# Shift_register.net
KiCad netlist of a schematic drawn in Altium Designer
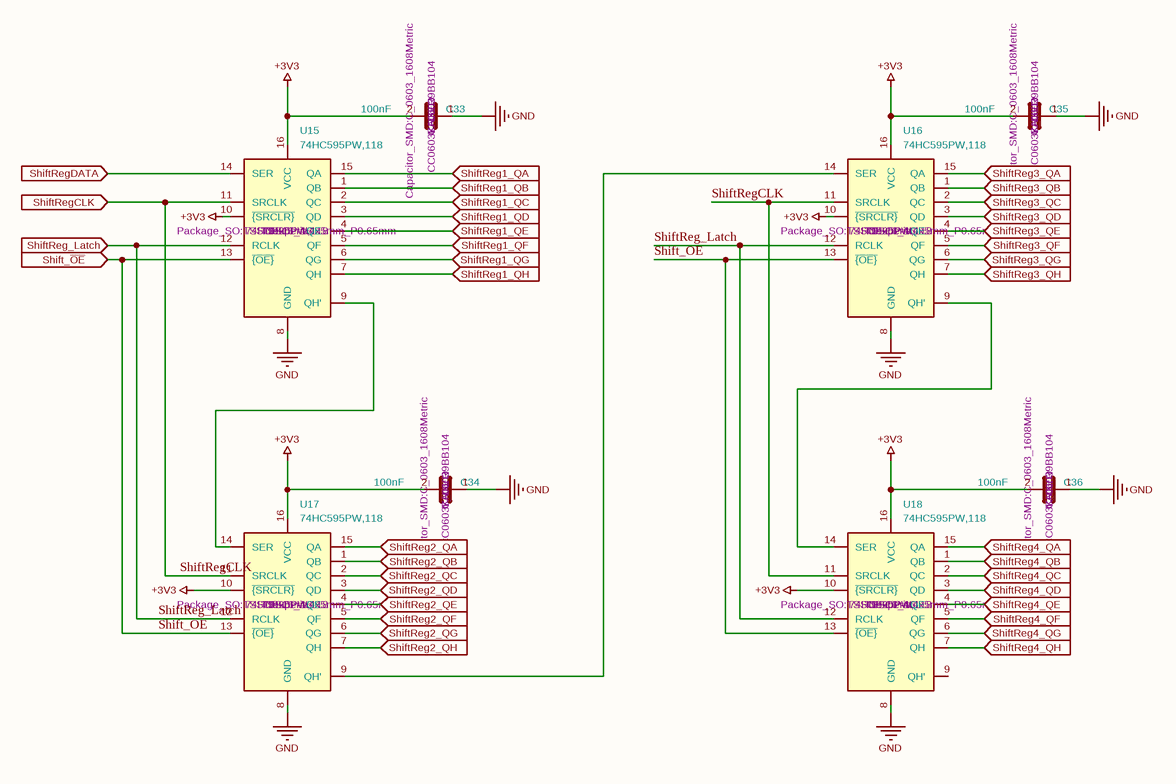
[diagram p0: Shift register.SchDoc]

(export (version "E")
  (design (tool "Eeschema 10.0.6"))
  (components
    (comp (ref "C33")
      (value "100nF")
      (footprint "Capacitor_SMD:C_0603_1608Metric")
      (fields
        (field (name "MANUFACTURER PART NUMBER") "CC0603KRX7R9BB104")
        (field (name "MANUFACTURER") "YAGEO")
        (field (name "PACKAGE") "C_0603")
      )
      (libsource (lib "Device") (part "C"))
    )
    (comp (ref "C34")
      (value "100nF")
      (footprint "Capacitor_SMD:C_0603_1608Metric")
      (fields
        (field (name "MANUFACTURER PART NUMBER") "CC0603KRX7R9BB104")
        (field (name "MANUFACTURER") "YAGEO")
        (field (name "PACKAGE") "C_0603")
      )
      (libsource (lib "Device") (part "C"))
    )
    (comp (ref "C35")
      (value "100nF")
      (footprint "Capacitor_SMD:C_0603_1608Metric")
      (fields
        (field (name "MANUFACTURER PART NUMBER") "CC0603KRX7R9BB104")
        (field (name "MANUFACTURER") "YAGEO")
        (field (name "PACKAGE") "C_0603")
      )
      (libsource (lib "Device") (part "C"))
    )
    (comp (ref "C36")
      (value "100nF")
      (footprint "Capacitor_SMD:C_0603_1608Metric")
      (fields
        (field (name "MANUFACTURER PART NUMBER") "CC0603KRX7R9BB104")
        (field (name "MANUFACTURER") "YAGEO")
        (field (name "PACKAGE") "C_0603")
      )
      (libsource (lib "Device") (part "C"))
    )
    (comp (ref "U15")
      (value "74HC595PW,118")
      (footprint "Package_SO:TSSOP-16_4.4x5mm_P0.65mm")
      (fields
        (field (name "MANUFACTURER PART NUMBER") "74HC595PW,118")
        (field (name "MANUFACTURER") "Nexperia")
        (field (name "PACKAGE") "TSSOP-16")
      )
      (libsource (lib "74xx") (part "74HC595"))
    )
    (comp (ref "U16")
      (value "74HC595PW,118")
      (footprint "Package_SO:TSSOP-16_4.4x5mm_P0.65mm")
      (fields
        (field (name "MANUFACTURER PART NUMBER") "74HC595PW,118")
        (field (name "MANUFACTURER") "Nexperia")
        (field (name "PACKAGE") "TSSOP-16")
      )
      (libsource (lib "74xx") (part "74HC595"))
    )
    (comp (ref "U17")
      (value "74HC595PW,118")
      (footprint "Package_SO:TSSOP-16_4.4x5mm_P0.65mm")
      (fields
        (field (name "MANUFACTURER PART NUMBER") "74HC595PW,118")
        (field (name "MANUFACTURER") "Nexperia")
        (field (name "PACKAGE") "TSSOP-16")
      )
      (libsource (lib "74xx") (part "74HC595"))
    )
    (comp (ref "U18")
      (value "74HC595PW,118")
      (footprint "Package_SO:TSSOP-16_4.4x5mm_P0.65mm")
      (fields
        (field (name "MANUFACTURER PART NUMBER") "74HC595PW,118")
        (field (name "MANUFACTURER") "Nexperia")
        (field (name "PACKAGE") "TSSOP-16")
      )
      (libsource (lib "74xx") (part "74HC595"))
    )
  )
  (nets
    (net (code "1") (name "+3V3") (class "Default")
      (node (ref "C33") (pin "2") (pinfunction "2_2") (pintype "passive"))
      (node (ref "C34") (pin "2") (pinfunction "2_2") (pintype "passive"))
      (node (ref "C35") (pin "2") (pinfunction "2_2") (pintype "passive"))
      (node (ref "C36") (pin "2") (pinfunction "2_2") (pintype "passive"))
      (node (ref "U15") (pin "10") (pinfunction "~{{SRCLR}}_10") (pintype "passive"))
      (node (ref "U15") (pin "16") (pinfunction "VCC_16") (pintype "passive"))
      (node (ref "U16") (pin "10") (pinfunction "~{{SRCLR}}_10") (pintype "passive"))
      (node (ref "U16") (pin "16") (pinfunction "VCC_16") (pintype "passive"))
      (node (ref "U17") (pin "10") (pinfunction "~{{SRCLR}}_10") (pintype "passive"))
      (node (ref "U17") (pin "16") (pinfunction "VCC_16") (pintype "passive"))
      (node (ref "U18") (pin "10") (pinfunction "~{{SRCLR}}_10") (pintype "passive"))
      (node (ref "U18") (pin "16") (pinfunction "VCC_16") (pintype "passive"))
    )
    (net (code "2") (name "/ShiftReg1_QA") (class "Default")
      (node (ref "U15") (pin "15") (pinfunction "QA_15") (pintype "passive"))
    )
    (net (code "3") (name "/ShiftReg1_QB") (class "Default")
      (node (ref "U15") (pin "1") (pinfunction "QB_1") (pintype "passive"))
    )
    (net (code "4") (name "/ShiftReg1_QC") (class "Default")
      (node (ref "U15") (pin "2") (pinfunction "QC_2") (pintype "passive"))
    )
    (net (code "5") (name "/ShiftReg1_QD") (class "Default")
      (node (ref "U15") (pin "3") (pinfunction "QD_3") (pintype "passive"))
    )
    (net (code "6") (name "/ShiftReg1_QE") (class "Default")
      (node (ref "U15") (pin "4") (pinfunction "QE_4") (pintype "passive"))
    )
    (net (code "7") (name "/ShiftReg1_QF") (class "Default")
      (node (ref "U15") (pin "5") (pinfunction "QF_5") (pintype "passive"))
    )
    (net (code "8") (name "/ShiftReg1_QG") (class "Default")
      (node (ref "U15") (pin "6") (pinfunction "QG_6") (pintype "passive"))
    )
    (net (code "9") (name "/ShiftReg1_QH") (class "Default")
      (node (ref "U15") (pin "7") (pinfunction "QH_7") (pintype "passive"))
    )
    (net (code "10") (name "/ShiftReg2_QA") (class "Default")
      (node (ref "U17") (pin "15") (pinfunction "QA_15") (pintype "passive"))
    )
    (net (code "11") (name "/ShiftReg2_QB") (class "Default")
      (node (ref "U17") (pin "1") (pinfunction "QB_1") (pintype "passive"))
    )
    (net (code "12") (name "/ShiftReg2_QC") (class "Default")
      (node (ref "U17") (pin "2") (pinfunction "QC_2") (pintype "passive"))
    )
    (net (code "13") (name "/ShiftReg2_QD") (class "Default")
      (node (ref "U17") (pin "3") (pinfunction "QD_3") (pintype "passive"))
    )
    (net (code "14") (name "/ShiftReg2_QE") (class "Default")
      (node (ref "U17") (pin "4") (pinfunction "QE_4") (pintype "passive"))
    )
    (net (code "15") (name "/ShiftReg2_QF") (class "Default")
      (node (ref "U17") (pin "5") (pinfunction "QF_5") (pintype "passive"))
    )
    (net (code "16") (name "/ShiftReg2_QG") (class "Default")
      (node (ref "U17") (pin "6") (pinfunction "QG_6") (pintype "passive"))
    )
    (net (code "17") (name "/ShiftReg2_QH") (class "Default")
      (node (ref "U17") (pin "7") (pinfunction "QH_7") (pintype "passive"))
    )
    (net (code "18") (name "/ShiftReg3_QA") (class "Default")
      (node (ref "U16") (pin "15") (pinfunction "QA_15") (pintype "passive"))
    )
    (net (code "19") (name "/ShiftReg3_QB") (class "Default")
      (node (ref "U16") (pin "1") (pinfunction "QB_1") (pintype "passive"))
    )
    (net (code "20") (name "/ShiftReg3_QC") (class "Default")
      (node (ref "U16") (pin "2") (pinfunction "QC_2") (pintype "passive"))
    )
    (net (code "21") (name "/ShiftReg3_QD") (class "Default")
      (node (ref "U16") (pin "3") (pinfunction "QD_3") (pintype "passive"))
    )
    (net (code "22") (name "/ShiftReg3_QE") (class "Default")
      (node (ref "U16") (pin "4") (pinfunction "QE_4") (pintype "passive"))
    )
    (net (code "23") (name "/ShiftReg3_QF") (class "Default")
      (node (ref "U16") (pin "5") (pinfunction "QF_5") (pintype "passive"))
    )
    (net (code "24") (name "/ShiftReg3_QG") (class "Default")
      (node (ref "U16") (pin "6") (pinfunction "QG_6") (pintype "passive"))
    )
    (net (code "25") (name "/ShiftReg3_QH") (class "Default")
      (node (ref "U16") (pin "7") (pinfunction "QH_7") (pintype "passive"))
    )
    (net (code "26") (name "/ShiftReg4_QA") (class "Default")
      (node (ref "U18") (pin "15") (pinfunction "QA_15") (pintype "passive"))
    )
    (net (code "27") (name "/ShiftReg4_QB") (class "Default")
      (node (ref "U18") (pin "1") (pinfunction "QB_1") (pintype "passive"))
    )
    (net (code "28") (name "/ShiftReg4_QC") (class "Default")
      (node (ref "U18") (pin "2") (pinfunction "QC_2") (pintype "passive"))
    )
    (net (code "29") (name "/ShiftReg4_QD") (class "Default")
      (node (ref "U18") (pin "3") (pinfunction "QD_3") (pintype "passive"))
    )
    (net (code "30") (name "/ShiftReg4_QE") (class "Default")
      (node (ref "U18") (pin "4") (pinfunction "QE_4") (pintype "passive"))
    )
    (net (code "31") (name "/ShiftReg4_QF") (class "Default")
      (node (ref "U18") (pin "5") (pinfunction "QF_5") (pintype "passive"))
    )
    (net (code "32") (name "/ShiftReg4_QG") (class "Default")
      (node (ref "U18") (pin "6") (pinfunction "QG_6") (pintype "passive"))
    )
    (net (code "33") (name "/ShiftReg4_QH") (class "Default")
      (node (ref "U18") (pin "7") (pinfunction "QH_7") (pintype "passive"))
    )
    (net (code "34") (name "/ShiftRegCLK") (class "Default")
      (node (ref "U15") (pin "11") (pinfunction "SRCLK_11") (pintype "passive"))
      (node (ref "U16") (pin "11") (pinfunction "SRCLK_11") (pintype "passive"))
      (node (ref "U17") (pin "11") (pinfunction "SRCLK_11") (pintype "passive"))
      (node (ref "U18") (pin "11") (pinfunction "SRCLK_11") (pintype "passive"))
    )
    (net (code "35") (name "/ShiftRegDATA") (class "Default")
      (node (ref "U15") (pin "14") (pinfunction "SER_14") (pintype "passive"))
    )
    (net (code "36") (name "/ShiftReg_Latch") (class "Default")
      (node (ref "U15") (pin "12") (pinfunction "RCLK_12") (pintype "passive"))
      (node (ref "U16") (pin "12") (pinfunction "RCLK_12") (pintype "passive"))
      (node (ref "U17") (pin "12") (pinfunction "RCLK_12") (pintype "passive"))
      (node (ref "U18") (pin "12") (pinfunction "RCLK_12") (pintype "passive"))
    )
    (net (code "37") (name "/Shift_~{OE}") (class "Default")
      (node (ref "U15") (pin "13") (pinfunction "~{{OE}}_13") (pintype "passive"))
      (node (ref "U16") (pin "13") (pinfunction "~{{OE}}_13") (pintype "passive"))
      (node (ref "U17") (pin "13") (pinfunction "~{{OE}}_13") (pintype "passive"))
      (node (ref "U18") (pin "13") (pinfunction "~{{OE}}_13") (pintype "passive"))
    )
    (net (code "38") (name "GND") (class "Default")
      (node (ref "C33") (pin "1") (pinfunction "1_1") (pintype "passive"))
      (node (ref "C34") (pin "1") (pinfunction "1_1") (pintype "passive"))
      (node (ref "C35") (pin "1") (pinfunction "1_1") (pintype "passive"))
      (node (ref "C36") (pin "1") (pinfunction "1_1") (pintype "passive"))
      (node (ref "U15") (pin "8") (pinfunction "GND_8") (pintype "passive"))
      (node (ref "U16") (pin "8") (pinfunction "GND_8") (pintype "passive"))
      (node (ref "U17") (pin "8") (pinfunction "GND_8") (pintype "passive"))
      (node (ref "U18") (pin "8") (pinfunction "GND_8") (pintype "passive"))
    )
    (net (code "39") (name "Net-(U15-QH')") (class "Default")
      (node (ref "U15") (pin "9") (pinfunction "QH'_9") (pintype "passive"))
      (node (ref "U17") (pin "14") (pinfunction "SER_14") (pintype "passive"))
    )
    (net (code "40") (name "Net-(U16-QH')") (class "Default")
      (node (ref "U16") (pin "9") (pinfunction "QH'_9") (pintype "passive"))
      (node (ref "U18") (pin "14") (pinfunction "SER_14") (pintype "passive"))
    )
    (net (code "41") (name "Net-(U16-SER)") (class "Default")
      (node (ref "U16") (pin "14") (pinfunction "SER_14") (pintype "passive"))
      (node (ref "U17") (pin "9") (pinfunction "QH'_9") (pintype "passive"))
    )
    (net (code "42") (name "unconnected-(U18-QH'-Pad9)") (class "Default")
      (node (ref "U18") (pin "9") (pinfunction "QH'_9") (pintype "passive"))
    )
  )
)
